# camera.net
KiCad netlist of a schematic drawn in Altium Designer
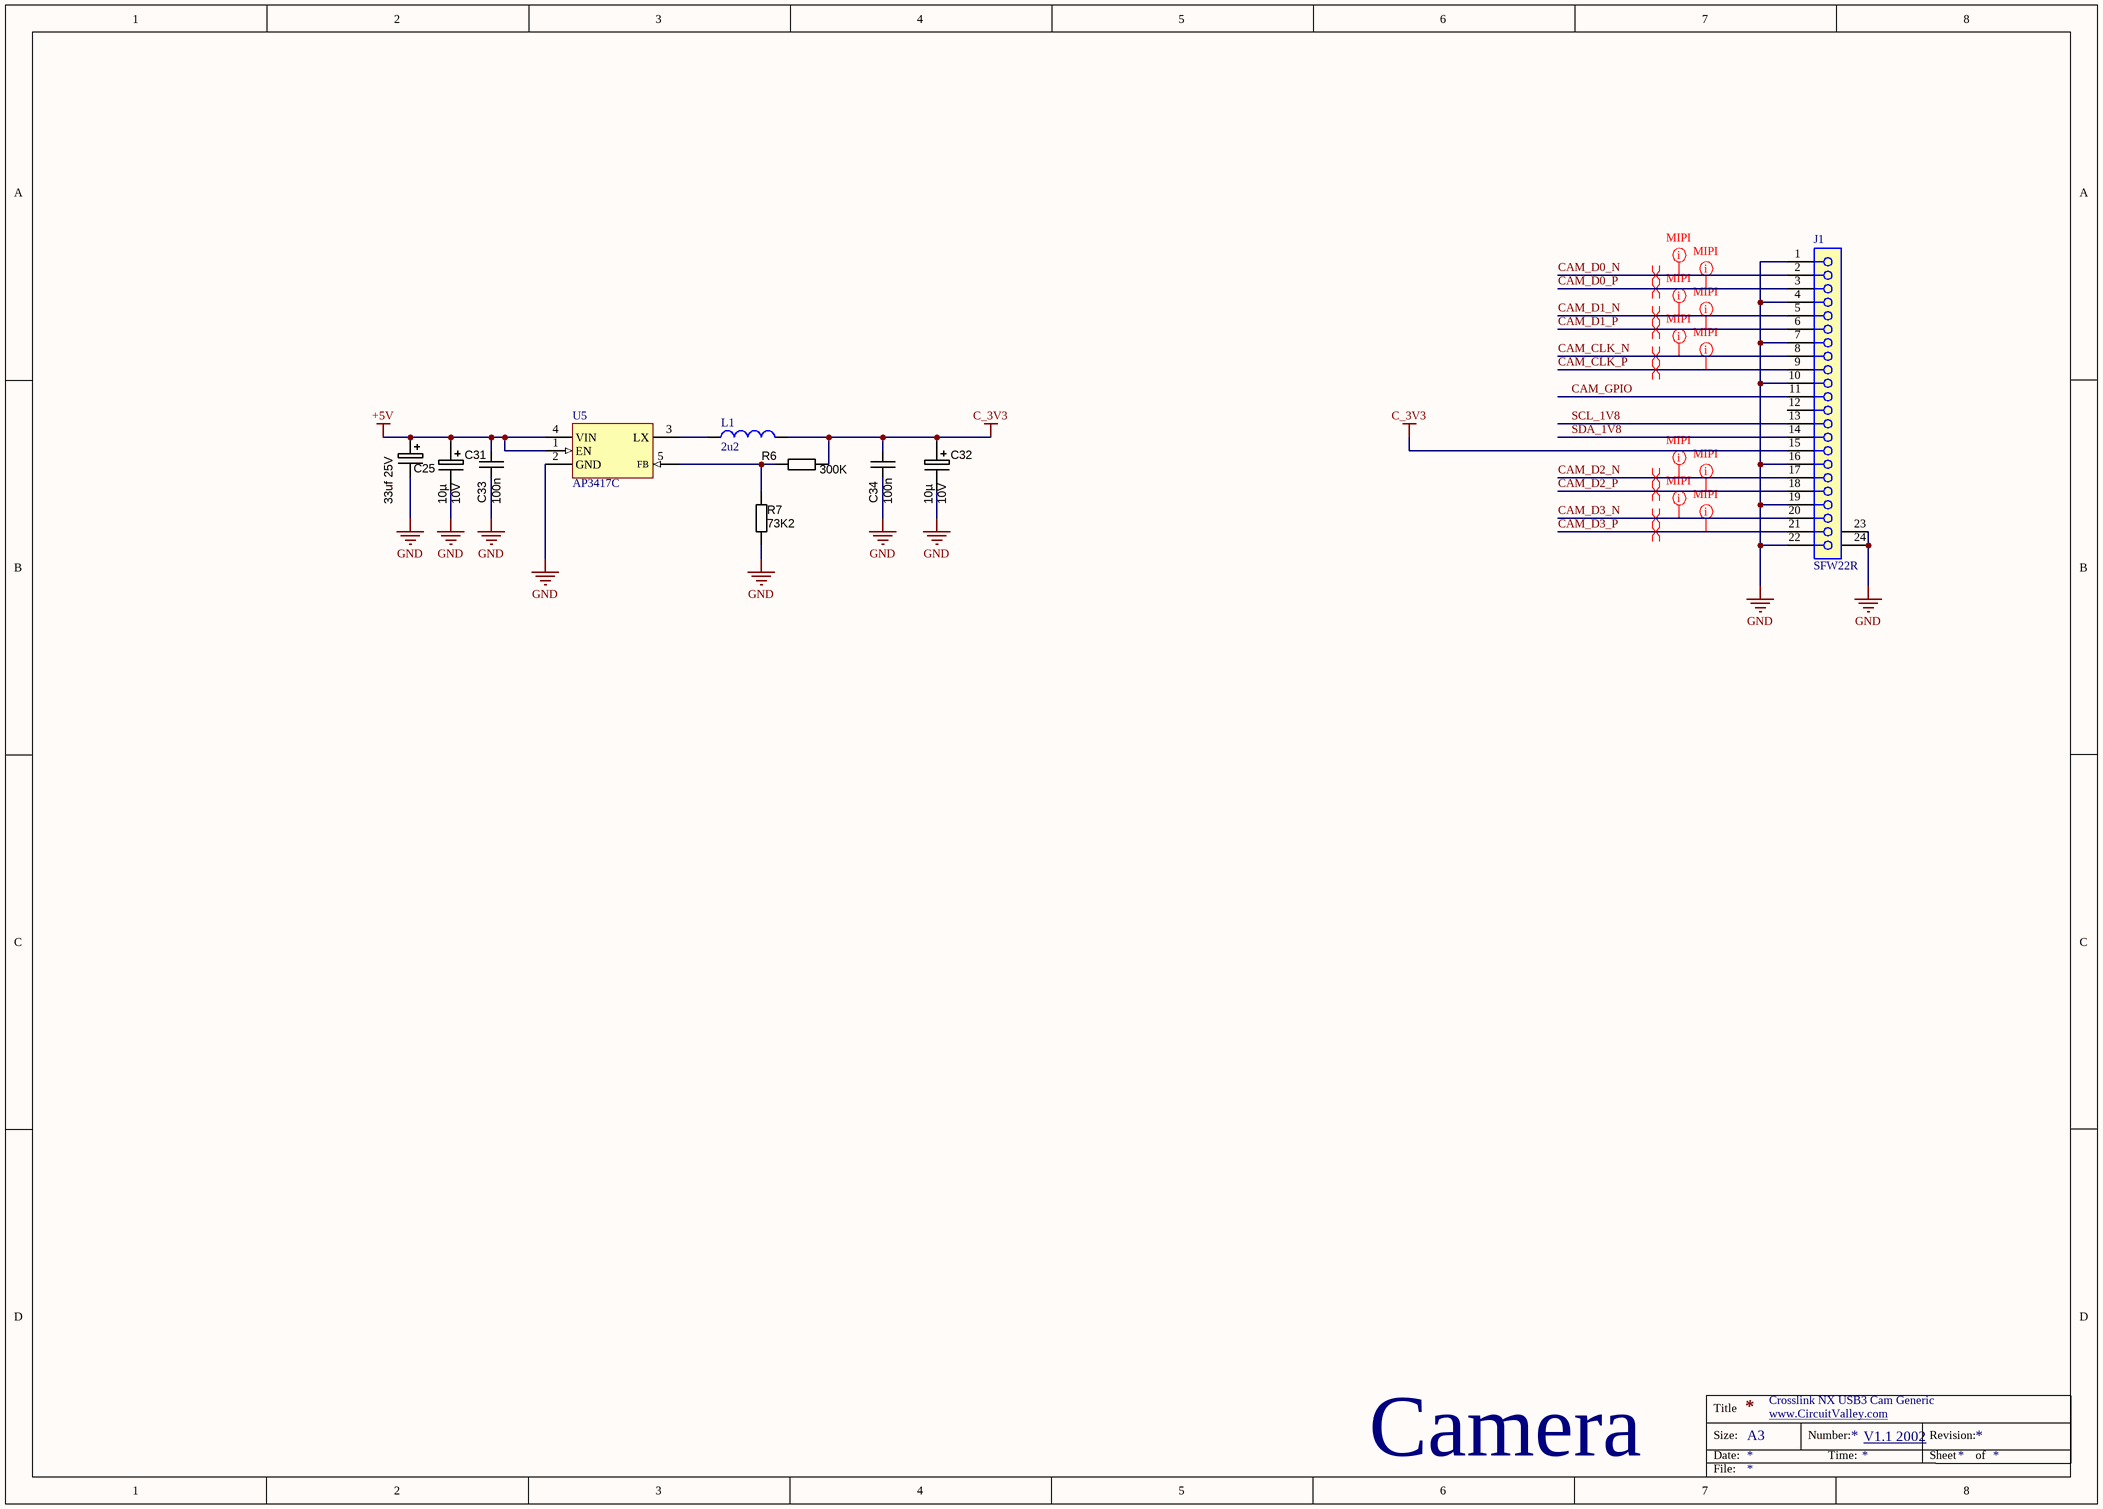
[diagram p0: camera.SchDoc]

(export (version "E")
  (design (tool "Eeschema 10.0.6"))
  (components
    (comp (ref "C25")
      (value "33uf 25V")
      (footprint "CAPMP7343X310N")
      (description "Capacitor SMD Tant 330uF 20% 6V3 2917")
      (fields
        (field (name "TOLERANCE") "±20%")
        (field (name "MANUFACTURER PART NUMBER") "T520D337M006ATE015")
      )
      (libsource (lib "PBL - Capacitors") (part "CAPT_330u_2917_6V3"))
    )
    (comp (ref "C31")
      (value "10µ")
      (footprint "CAPMP3528X210N")
      (description "Capacitor SMD Tantalum 47uF 20% 6.3V 1210")
      (fields (field (name "TOLERANCE") "±20%") (field (name "RATINGS") "10V"))
      (libsource (lib "PBL - Capacitors") (part "CAPT_47u_1210_6V3"))
    )
    (comp (ref "C32")
      (value "10µ")
      (footprint "CAPMP3528X210N")
      (description "Capacitor SMD Tantalum 47uF 20% 6.3V 1210")
      (fields (field (name "TOLERANCE") "±20%") (field (name "RATINGS") "10V"))
      (libsource (lib "PBL - Capacitors") (part "CAPT_47u_1210_6V3"))
    )
    (comp (ref "C33")
      (value "100n")
      (footprint "CAPC1608N")
      (description "Capacitor SMD Cer 10pF 5% 50V NP0 0603")
      (fields (field (name "TOLERANCE") "±5%") (field (name "PART") "C0603X104K5RAC"))
      (libsource (lib "PBL - Capacitors") (part "CAPC_10p_0603_NP0_1%_50V"))
    )
    (comp (ref "C34")
      (value "100n")
      (footprint "CAPC1608N")
      (description "Capacitor SMD Cer 10pF 5% 50V NP0 0603")
      (fields (field (name "TOLERANCE") "±5%") (field (name "PART") "C0603X104K5RAC"))
      (libsource (lib "PBL - Capacitors") (part "CAPC_10p_0603_NP0_1%_50V"))
    )
    (comp (ref "J1")
      (value "SFW22R")
      (footprint "SFW22R")
      (description "22 Pin FPC")
      (libsource (lib "FCI_FPC") (part "SFW22R"))
    )
    (comp (ref "L1")
      (value "2u2")
      (footprint "TAIYO_NRS4018T2R2MDGJ")
      (fields (field (name "PARTNUMBER") "NRS4018T2R2MDGJ"))
      (libsource (lib "Inductor") (part "inductor_smd"))
    )
    (comp (ref "R6")
      (value "300K")
      (footprint "RESC1608N_ZERO")
      (description "Resistor SMD chip 0.0 Ohm 0.1W 0603")
      (fields (field (name "TOLERANCE") "±5%") (field (name "Comment") "Thick Film"))
      (libsource (lib "PBL - Resistors") (part "RES_0R_0603"))
    )
    (comp (ref "R7")
      (value "73K2")
      (footprint "RESC1608N_ZERO")
      (description "Resistor SMD chip 0.0 Ohm 0.1W 0603")
      (fields (field (name "TOLERANCE") "±5%") (field (name "Comment") "Thick Film"))
      (libsource (lib "") (part "RES_0R_0603_1"))
    )
    (comp (ref "U5") (value "AP3417C") (footprint "SOT23-5") (libsource (lib "cvlib") (part "AP3417C")))
  )
  (nets
    (net (code "1") (name "+5V") (class "Default")
      (node (ref "C25") (pin "1") (pintype "passive"))
      (node (ref "C31") (pin "1") (pintype "passive"))
      (node (ref "C33") (pin "2") (pintype "passive"))
      (node (ref "U5") (pin "1") (pinfunction "EN_1") (pintype "input"))
      (node (ref "U5") (pin "4") (pinfunction "VIN_4") (pintype "power_in"))
    )
    (net (code "2") (name "/CAM_CLK_N") (class "Default")
      (node (ref "J1") (pin "8") (pinfunction "8_8") (pintype "passive"))
    )
    (net (code "3") (name "/CAM_CLK_P") (class "Default")
      (node (ref "J1") (pin "9") (pinfunction "9_9") (pintype "passive"))
    )
    (net (code "4") (name "/CAM_D0_N") (class "Default")
      (node (ref "J1") (pin "2") (pinfunction "2_2") (pintype "passive"))
    )
    (net (code "5") (name "/CAM_D0_P") (class "Default")
      (node (ref "J1") (pin "3") (pinfunction "3_3") (pintype "passive"))
    )
    (net (code "6") (name "/CAM_D1_N") (class "Default")
      (node (ref "J1") (pin "5") (pinfunction "5_5") (pintype "passive"))
    )
    (net (code "7") (name "/CAM_D1_P") (class "Default")
      (node (ref "J1") (pin "6") (pinfunction "6_6") (pintype "passive"))
    )
    (net (code "8") (name "/CAM_D2_N") (class "Default")
      (node (ref "J1") (pin "17") (pinfunction "17_17") (pintype "passive"))
    )
    (net (code "9") (name "/CAM_D2_P") (class "Default")
      (node (ref "J1") (pin "18") (pinfunction "18_18") (pintype "passive"))
    )
    (net (code "10") (name "/CAM_D3_N") (class "Default")
      (node (ref "J1") (pin "20") (pinfunction "20_20") (pintype "passive"))
    )
    (net (code "11") (name "/CAM_D3_P") (class "Default")
      (node (ref "J1") (pin "21") (pinfunction "21_21") (pintype "passive"))
    )
    (net (code "12") (name "/CAM_GPIO") (class "Default")
      (node (ref "J1") (pin "11") (pinfunction "11_11") (pintype "passive"))
    )
    (net (code "13") (name "/SCL_1V8") (class "Default")
      (node (ref "J1") (pin "13") (pinfunction "13_13") (pintype "passive"))
    )
    (net (code "14") (name "/SDA_1V8") (class "Default")
      (node (ref "J1") (pin "14") (pinfunction "14_14") (pintype "passive"))
    )
    (net (code "15") (name "C_3V3") (class "Default")
      (node (ref "C32") (pin "1") (pintype "passive"))
      (node (ref "C34") (pin "2") (pintype "passive"))
      (node (ref "J1") (pin "15") (pinfunction "15_15") (pintype "passive"))
      (node (ref "L1") (pin "2") (pinfunction "2_2") (pintype "passive"))
      (node (ref "R6") (pin "1") (pinfunction "1_1") (pintype "passive"))
    )
    (net (code "16") (name "GND") (class "Default")
      (node (ref "C25") (pin "2") (pintype "passive"))
      (node (ref "C31") (pin "2") (pintype "passive"))
      (node (ref "C32") (pin "2") (pintype "passive"))
      (node (ref "C33") (pin "1") (pintype "passive"))
      (node (ref "C34") (pin "1") (pintype "passive"))
      (node (ref "J1") (pin "1") (pinfunction "1_1") (pintype "passive"))
      (node (ref "J1") (pin "10") (pinfunction "10_10") (pintype "passive"))
      (node (ref "J1") (pin "16") (pinfunction "16_16") (pintype "passive"))
      (node (ref "J1") (pin "19") (pinfunction "19_19") (pintype "passive"))
      (node (ref "J1") (pin "22") (pinfunction "22_22") (pintype "passive"))
      (node (ref "J1") (pin "23") (pinfunction "23_23") (pintype "passive"))
      (node (ref "J1") (pin "24") (pinfunction "24_24") (pintype "passive"))
      (node (ref "J1") (pin "4") (pinfunction "4_4") (pintype "passive"))
      (node (ref "J1") (pin "7") (pinfunction "7_7") (pintype "passive"))
      (node (ref "R7") (pin "2") (pinfunction "2_2") (pintype "passive"))
      (node (ref "U5") (pin "2") (pinfunction "GND_2") (pintype "power_in"))
    )
    (net (code "17") (name "Net-(U5-FB)") (class "Default")
      (node (ref "R6") (pin "2") (pinfunction "2_2") (pintype "passive"))
      (node (ref "R7") (pin "1") (pinfunction "1_1") (pintype "passive"))
      (node (ref "U5") (pin "5") (pinfunction "FB_5") (pintype "input"))
    )
    (net (code "18") (name "Net-(U5-LX)") (class "Default")
      (node (ref "L1") (pin "1") (pinfunction "1_1") (pintype "passive"))
      (node (ref "U5") (pin "3") (pinfunction "LX_3") (pintype "passive"))
    )
    (net (code "19") (name "unconnected-(J1-Pad12)") (class "Default")
      (node (ref "J1") (pin "12") (pinfunction "12_12") (pintype "passive"))
    )
  )
)
